# voeding.net
KiCad netlist of a schematic drawn in Altium Designer
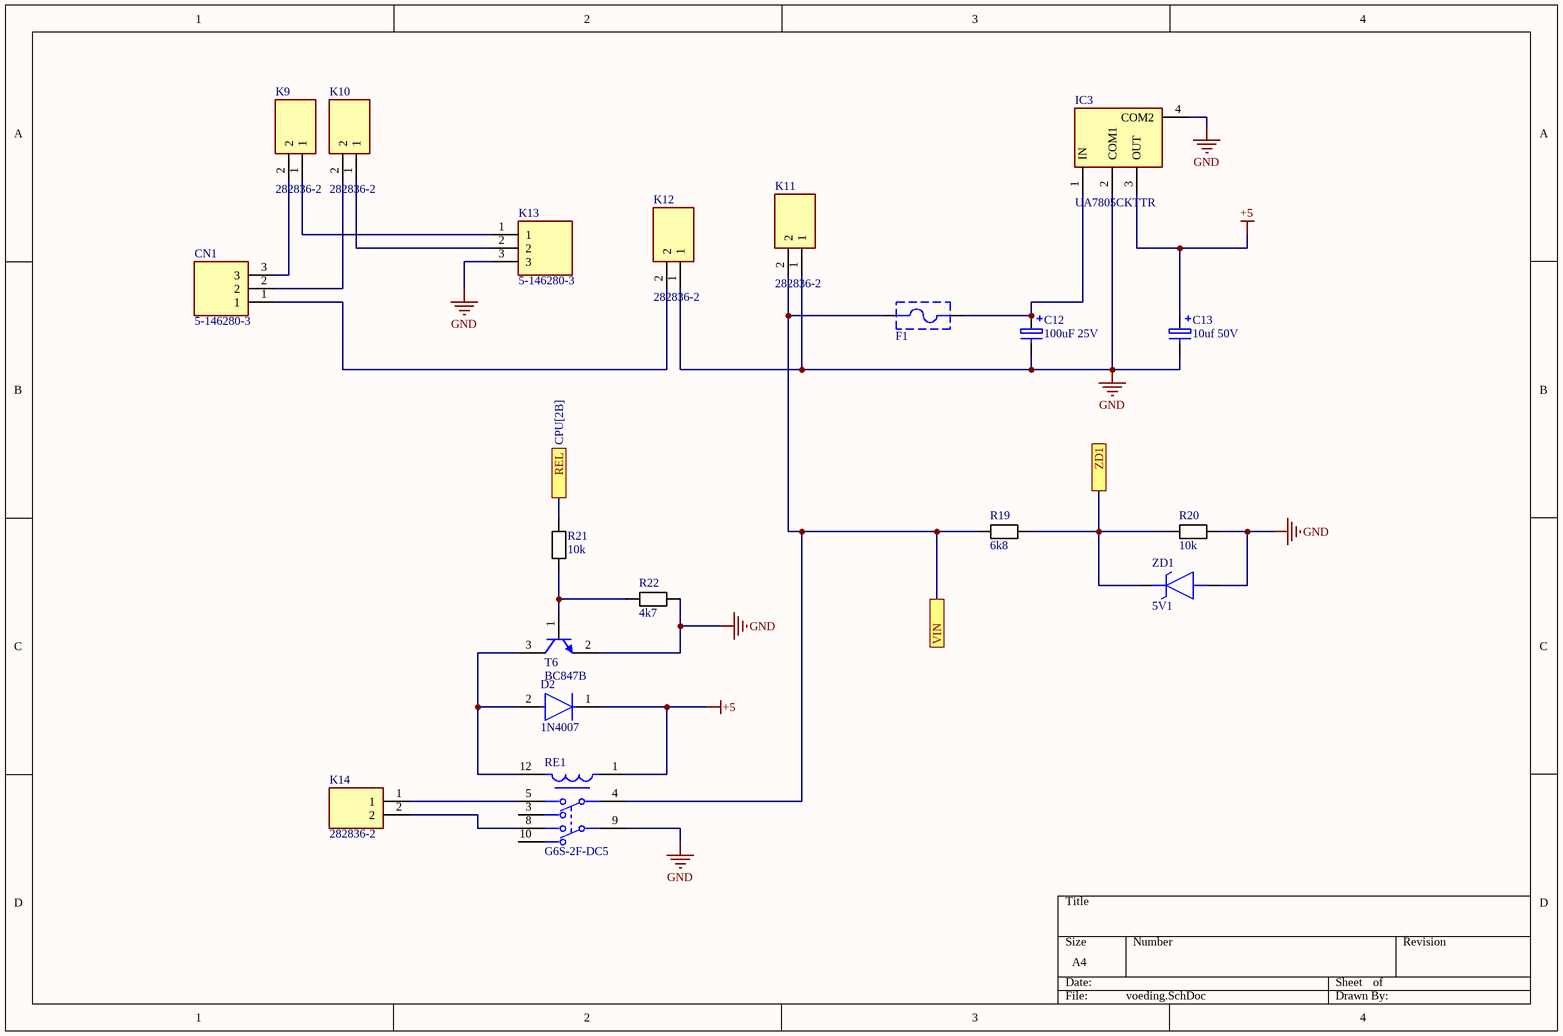
[diagram p0: voeding.SchDoc]

(export (version "E")
  (design (tool "Eeschema 10.0.6"))
  (components
    (comp (ref "C12")
      (value "100uF 25V")
      (footprint "Elco 100uF 25V")
      (fields
        (field (name "PART NUMBER") "02015A270JAT2A")
        (field (name "MANUFACTURER") "AVX Interconnect / Elco")
      )
      (libsource (lib "Schlib1") (part "Condensator 100uF 25V"))
    )
    (comp (ref "C13")
      (value "10uf 50V")
      (footprint "Elco 10uF 50V")
      (fields
        (field (name "PART NUMBER") "02015A270JAT2A")
        (field (name "MANUFACTURER") "AVX Interconnect / Elco")
      )
      (libsource (lib "Schlib1") (part "Condensator 10uf 50V"))
    )
    (comp (ref "CN1")
      (value "5-146280-3")
      (footprint "3 Pin Header")
      (description "Connector 5-146280-3")
      (fields (field (name "MOUSER2 PART NUMBER") "571-5-146280-3"))
      (libsource (lib "Schlib1") (part "3 Pin Header"))
    )
    (comp (ref "D2")
      (value "1N4007")
      (footprint "1N4007")
      (description "Rectifier diode 1000 V 1 A DO-41, ,")
      (fields
        (field (name "MANUFACTURER") "Diotec")
        (field (name "OCTOPART") "https://octopart.com/1n4007-diotec-4040411")
      )
      (libsource (lib "soldeerstation") (part "1N4007"))
    )
    (comp (ref "F1")
      (value "696101000002")
      (footprint "zekeringhouder")
      (description "WR-FSH Fuseholder THT Blocks PCB Clip Cover")
      (fields (field (name "MANUFACTURER") "Wurth Elektronik"))
      (libsource (lib "soldeerstation") (part "zekeringhouder"))
    )
    (comp (ref "IC3")
      (value "UA7805CKTTR")
      (footprint "FP-KTT0003A-MFG")
      (description "IC REG LIN 5V 1.5A DDPAK/TO263-3")
      (libsource (lib "soldeerstation") (part "IC4"))
    )
    (comp (ref "K9")
      (value "282836-2")
      (footprint "Schroefconnector 2 Pin")
      (description "Connector")
      (libsource (lib "soldeerstation") (part "Schroefconnector 2 Pin L"))
    )
    (comp (ref "K10")
      (value "282836-2")
      (footprint "Schroefconnector 2 Pin")
      (description "Connector")
      (libsource (lib "soldeerstation") (part "Schroefconnector 2 Pin L"))
    )
    (comp (ref "K11")
      (value "282836-2")
      (footprint "Schroefconnector 2 Pin")
      (description "Connector")
      (libsource (lib "soldeerstation") (part "Schroefconnector 2 Pin L"))
    )
    (comp (ref "K12")
      (value "282836-2")
      (footprint "Schroefconnector 2 Pin")
      (description "Connector")
      (libsource (lib "soldeerstation") (part "Schroefconnector 2 Pin L"))
    )
    (comp (ref "K13")
      (value "5-146280-3")
      (footprint "3 Pin Header")
      (description "Connector 5-146280-3")
      (fields (field (name "MOUSER2 PART NUMBER") "571-5-146280-3"))
      (libsource (lib "soldeerstation") (part "3 Pin Header L"))
    )
    (comp (ref "K14")
      (value "282836-2")
      (footprint "Schroefconnector 2 Pin")
      (description "Connector")
      (libsource (lib "") (part "Schroefconnector 2 Pin L_1"))
    )
    (comp (ref "R19")
      (value "6k8")
      (footprint "registor")
      (fields (field (name "MANUFACTURER") "Vishay Dale") (field (name "PART NUMBER") "CRCW08050000Z0EA"))
      (libsource (lib "Schlib1") (part "resistor"))
    )
    (comp (ref "R20")
      (value "10k")
      (footprint "registor")
      (fields (field (name "MANUFACTURER") "Vishay Dale") (field (name "PART NUMBER") "CRCW08050000Z0EA"))
      (libsource (lib "Schlib1") (part "resistor"))
    )
    (comp (ref "R21")
      (value "10k")
      (footprint "registor")
      (fields (field (name "MANUFACTURER") "Vishay Dale") (field (name "PART NUMBER") "CRCW08050000Z0EA"))
      (libsource (lib "Schlib1") (part "resistor"))
    )
    (comp (ref "R22")
      (value "4k7")
      (footprint "registor")
      (fields (field (name "MANUFACTURER") "Vishay Dale") (field (name "PART NUMBER") "CRCW08050000Z0EA"))
      (libsource (lib "Schlib1") (part "resistor"))
    )
    (comp (ref "RE1")
      (value "G6S-2F-DC5")
      (footprint "FP-G6S-2F-DC5-MFG")
      (description "RELAY TELECOM DPDT 2A 5VDC")
      (fields
        (field (name "MANUFACTURER") "Omron")
        (field (name "OCTOPART") "https://octopart.com/g6s-2f-dc5-omron-85236")
      )
      (libsource (lib "soldeerstation") (part "CMP-08823-000012-1"))
    )
    (comp (ref "T6")
      (value "BC847B")
      (footprint "INF-SOT23_L")
      (description "NPN Silicon AF Transistor, 45 V VCEO, 100 mA IC, SOT23, Reel, Green")
      (fields (field (name "MANUFACTURER") "Infineon"))
      (libsource (lib "soldeerstation") (part "BC847B"))
    )
    (comp (ref "ZD1")
      (value "5V1")
      (footprint "SOD3716X135N")
      (description "Zener Diode")
      (fields
        (field (name "MANUFACTURER_PART_NUMBER") "MMSZ4689T1G")
        (field (name "MOUSER PART NUMBER") "863-MMSZ4689T1G")
      )
      (libsource (lib "soldeerstation") (part "MMSZ4689T1G"))
    )
  )
  (nets
    (net (code "1") (name "+5") (class "Default")
      (node (ref "C13") (pin "1") (pinfunction "1_1") (pintype "passive"))
      (node (ref "D2") (pin "1") (pinfunction "C_1") (pintype "passive"))
      (node (ref "IC3") (pin "3") (pinfunction "OUT_3") (pintype "power_in"))
      (node (ref "RE1") (pin "1") (pinfunction "1_1") (pintype "passive"))
    )
    (net (code "2") (name "/REL") (class "Default")
      (node (ref "R21") (pin "2") (pinfunction "2_2") (pintype "passive"))
    )
    (net (code "3") (name "/VIN") (class "Default")
      (node (ref "F1") (pin "1") (pinfunction "1_1") (pintype "passive"))
      (node (ref "K11") (pin "2") (pinfunction "2_2") (pintype "passive"))
      (node (ref "R19") (pin "1") (pinfunction "1_1") (pintype "passive"))
      (node (ref "RE1") (pin "4") (pinfunction "4_4") (pintype "passive"))
    )
    (net (code "4") (name "/ZD1") (class "Default")
      (node (ref "R19") (pin "2") (pinfunction "2_2") (pintype "passive"))
      (node (ref "R20") (pin "1") (pinfunction "1_1") (pintype "passive"))
      (node (ref "ZD1") (pin "1") (pinfunction "K_1") (pintype "passive"))
    )
    (net (code "5") (name "GND") (class "Default")
      (node (ref "C12") (pin "2") (pinfunction "2_2") (pintype "passive"))
      (node (ref "C13") (pin "2") (pinfunction "2_2") (pintype "passive"))
      (node (ref "IC3") (pin "2") (pinfunction "COM1_2") (pintype "power_in"))
      (node (ref "IC3") (pin "4") (pinfunction "COM2_4") (pintype "power_in"))
      (node (ref "K11") (pin "1") (pinfunction "1_1") (pintype "passive"))
      (node (ref "K12") (pin "1") (pinfunction "1_1") (pintype "passive"))
      (node (ref "K13") (pin "3") (pinfunction "3_3") (pintype "passive"))
      (node (ref "R20") (pin "2") (pinfunction "2_2") (pintype "passive"))
      (node (ref "R22") (pin "2") (pinfunction "2_2") (pintype "passive"))
      (node (ref "RE1") (pin "9") (pinfunction "9_9") (pintype "passive"))
      (node (ref "T6") (pin "2") (pinfunction "E_2") (pintype "passive"))
      (node (ref "ZD1") (pin "2") (pinfunction "A_2") (pintype "passive"))
    )
    (net (code "6") (name "Net-(CN1-Pad1)") (class "Default")
      (node (ref "CN1") (pin "1") (pinfunction "1_1") (pintype "passive"))
      (node (ref "K12") (pin "2") (pinfunction "2_2") (pintype "passive"))
    )
    (net (code "7") (name "Net-(CN1-Pad2)") (class "Default")
      (node (ref "CN1") (pin "2") (pinfunction "2_2") (pintype "passive"))
      (node (ref "K10") (pin "2") (pinfunction "2_2") (pintype "passive"))
    )
    (net (code "8") (name "Net-(CN1-Pad3)") (class "Default")
      (node (ref "CN1") (pin "3") (pinfunction "3_3") (pintype "passive"))
      (node (ref "K9") (pin "2") (pinfunction "2_2") (pintype "passive"))
    )
    (net (code "9") (name "Net-(D2-A)") (class "Default")
      (node (ref "D2") (pin "2") (pinfunction "A_2") (pintype "passive"))
      (node (ref "RE1") (pin "12") (pinfunction "12_12") (pintype "passive"))
      (node (ref "T6") (pin "3") (pinfunction "C_3") (pintype "passive"))
    )
    (net (code "10") (name "Net-(IC3-IN)") (class "Default")
      (node (ref "C12") (pin "1") (pinfunction "1_1") (pintype "passive"))
      (node (ref "F1") (pin "2") (pinfunction "2_2") (pintype "passive"))
      (node (ref "IC3") (pin "1") (pinfunction "IN_1") (pintype "power_in"))
    )
    (net (code "11") (name "Net-(K10-Pad1)") (class "Default")
      (node (ref "K10") (pin "1") (pinfunction "1_1") (pintype "passive"))
      (node (ref "K13") (pin "2") (pinfunction "2_2") (pintype "passive"))
    )
    (net (code "12") (name "Net-(K13-Pad1)") (class "Default")
      (node (ref "K13") (pin "1") (pinfunction "1_1") (pintype "passive"))
      (node (ref "K9") (pin "1") (pinfunction "1_1") (pintype "passive"))
    )
    (net (code "13") (name "Net-(K14-Pad1)") (class "Default")
      (node (ref "K14") (pin "1") (pinfunction "1_1") (pintype "passive"))
      (node (ref "RE1") (pin "5") (pinfunction "5_5") (pintype "passive"))
    )
    (net (code "14") (name "Net-(K14-Pad2)") (class "Default")
      (node (ref "K14") (pin "2") (pinfunction "2_2") (pintype "passive"))
      (node (ref "RE1") (pin "8") (pinfunction "8_8") (pintype "passive"))
    )
    (net (code "15") (name "Net-(T6-B)") (class "Default")
      (node (ref "R21") (pin "1") (pinfunction "1_1") (pintype "passive"))
      (node (ref "R22") (pin "1") (pinfunction "1_1") (pintype "passive"))
      (node (ref "T6") (pin "1") (pinfunction "B_1") (pintype "passive"))
    )
    (net (code "16") (name "unconnected-(RE1-Pad3)") (class "Default")
      (node (ref "RE1") (pin "3") (pinfunction "3_3") (pintype "passive"))
    )
    (net (code "17") (name "unconnected-(RE1-Pad10)") (class "Default")
      (node (ref "RE1") (pin "10") (pinfunction "10_10") (pintype "passive"))
    )
  )
)
